# LCmeter0-LCD-6pin.net
KiCad netlist of a schematic drawn in EAGLE
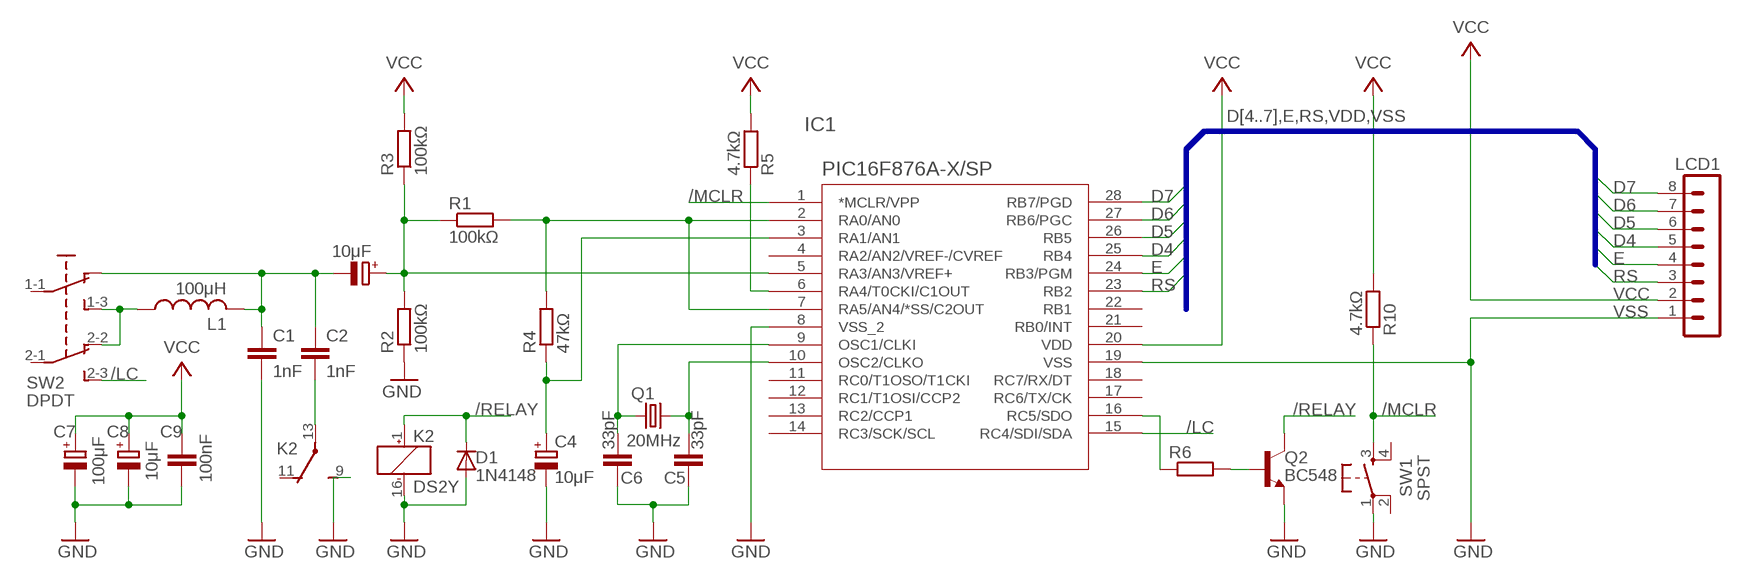
[diagram p0: schematic, sheet 1]

(export (version "E")
  (design (tool "Eeschema 10.0.6"))
  (components
    (comp (ref "C1")
      (value "1nF")
      (footprint "eagle-import:C050-025X075")
      (libsource (lib "eagle-import") (part "C-EU050-025X075"))
    )
    (comp (ref "C2")
      (value "1nF")
      (footprint "eagle-import:C050-025X075")
      (libsource (lib "eagle-import") (part "C-EU050-025X075"))
    )
    (comp (ref "C3")
      (value "10μF")
      (footprint "eagle-import:E2,5-6")
      (libsource (lib "eagle-import") (part "CPOL-EUE2.5-6"))
    )
    (comp (ref "C4")
      (value "10μF")
      (footprint "eagle-import:E5-6")
      (libsource (lib "eagle-import") (part "CPOL-EUE5-6"))
    )
    (comp (ref "C5")
      (value "33pF")
      (footprint "eagle-import:C050-025X075")
      (libsource (lib "eagle-import") (part "C-EU050-025X075"))
    )
    (comp (ref "C6")
      (value "33pF")
      (footprint "eagle-import:C050-025X075")
      (libsource (lib "eagle-import") (part "C-EU050-025X075"))
    )
    (comp (ref "C7")
      (value "100μF")
      (footprint "eagle-import:E2,5-6")
      (libsource (lib "eagle-import") (part "CPOL-EUE2.5-6"))
    )
    (comp (ref "C8")
      (value "10μF")
      (footprint "eagle-import:E2,5-5")
      (libsource (lib "eagle-import") (part "CPOL-EUE2.5-5"))
    )
    (comp (ref "C9")
      (value "100nF")
      (footprint "eagle-import:C025-024X044")
      (libsource (lib "eagle-import") (part "C-EU025-024X044"))
    )
    (comp (ref "D1")
      (value "1N4148")
      (footprint "eagle-import:DO35-7")
      (libsource (lib "eagle-import") (part "1N4148DO35-7"))
    )
    (comp (ref "IC1")
      (value "PIC16F876A-X/SP")
      (footprint "eagle-import:DIL28-3")
      (libsource (lib "eagle-import") (part "PIC16F876A-X/SP"))
    )
    (comp (ref "K2")
      (value "DS2Y")
      (footprint "eagle-import:DS2Y")
      (fields (field (name "MPN") "DS2Y-S-DC5V"))
      (libsource (lib "eagle-import") (part "DS2Y-S-DC5V"))
    )
    (comp (ref "L1")
      (value "100μH")
      (footprint "eagle-import:0207_10")
      (libsource (lib "eagle-import") (part "L-US0207/10"))
    )
    (comp (ref "LCD1")
      (value "MA08-1")
      (footprint "eagle-import:MA08-1")
      (libsource (lib "eagle-import") (part "MA08-1"))
    )
    (comp (ref "Q1")
      (value "20MHz")
      (footprint "eagle-import:HC49U70")
      (libsource (lib "eagle-import") (part "CRYSTALHC49U70"))
    )
    (comp (ref "Q2")
      (value "BC548")
      (footprint "eagle-import:TO92-EBC")
      (libsource (lib "eagle-import") (part "BC548"))
    )
    (comp (ref "R1")
      (value "100kΩ")
      (footprint "eagle-import:0207_10")
      (libsource (lib "eagle-import") (part "resistor_R-EU_0207/10"))
    )
    (comp (ref "R2")
      (value "100kΩ")
      (footprint "eagle-import:0207_10")
      (libsource (lib "eagle-import") (part "resistor_R-EU_0207/10"))
    )
    (comp (ref "R3")
      (value "100kΩ")
      (footprint "eagle-import:0204V")
      (libsource (lib "eagle-import") (part "resistor_R-EU_0204/2V"))
    )
    (comp (ref "R4")
      (value "47kΩ")
      (footprint "eagle-import:0207_10")
      (libsource (lib "eagle-import") (part "resistor_R-EU_0207/10"))
    )
    (comp (ref "R5")
      (value "4.7kΩ")
      (footprint "eagle-import:0204V")
      (libsource (lib "eagle-import") (part "resistor_R-EU_0204/2V"))
    )
    (comp (ref "R6")
      (value "R-EU_0207/10")
      (footprint "eagle-import:0207_10")
      (libsource (lib "eagle-import") (part "R-EU_0207/10"))
    )
    (comp (ref "R10")
      (value "4.7kΩ")
      (footprint "eagle-import:0204V")
      (libsource (lib "eagle-import") (part "resistor_R-EU_0204/2V"))
    )
    (comp (ref "SW1")
      (value "SPST")
      (footprint "eagle-import:PB-5")
      (libsource (lib "eagle-import") (part "PB-SPST"))
    )
    (comp (ref "SW2")
      (value "DPDT")
      (footprint "eagle-import:DPDT")
      (libsource (lib "eagle-import") (part "S-DPDT"))
    )
  )
  (nets
    (net (code "2") (name "/D4") (class "Default")
      (node (ref "IC1") (pin "25") (pinfunction "RB4_25") (pintype "passive"))
      (node (ref "LCD1") (pin "5") (pinfunction "5_5") (pintype "passive"))
    )
    (net (code "3") (name "/D5") (class "Default")
      (node (ref "IC1") (pin "26") (pinfunction "RB5_26") (pintype "passive"))
      (node (ref "LCD1") (pin "6") (pinfunction "6_6") (pintype "passive"))
    )
    (net (code "4") (name "/D6") (class "Default")
      (node (ref "IC1") (pin "27") (pinfunction "RB6/PGC_27") (pintype "passive"))
      (node (ref "LCD1") (pin "7") (pinfunction "7_7") (pintype "passive"))
    )
    (net (code "5") (name "/D7") (class "Default")
      (node (ref "IC1") (pin "28") (pinfunction "RB7/PGD_28") (pintype "passive"))
      (node (ref "LCD1") (pin "8") (pinfunction "8_8") (pintype "passive"))
    )
    (net (code "6") (name "/E") (class "Default")
      (node (ref "IC1") (pin "24") (pinfunction "RB3/PGM_24") (pintype "passive"))
      (node (ref "LCD1") (pin "4") (pinfunction "4_4") (pintype "passive"))
    )
    (net (code "7") (name "/RS") (class "Default")
      (node (ref "IC1") (pin "23") (pinfunction "RB2_23") (pintype "passive"))
      (node (ref "LCD1") (pin "3") (pinfunction "3_3") (pintype "passive"))
    )
    (net (code "9") (name "/{slash}LC") (class "Default")
      (node (ref "IC1") (pin "15") (pinfunction "RC4/SDI/SDA_15") (pintype "passive"))
      (node (ref "SW2") (pin "2-3") (pinfunction "2-3_2-3") (pintype "passive"))
    )
    (net (code "10") (name "/{slash}MCLR") (class "Default")
      (node (ref "IC1") (pin "1") (pinfunction "*MCLR/VPP_1") (pintype "passive"))
      (node (ref "R10") (pin "1") (pinfunction "1_1") (pintype "passive"))
      (node (ref "SW1") (pin "3") (pinfunction "S_3") (pintype "passive"))
    )
    (net (code "11") (name "/{slash}RELAY") (class "Default")
      (node (ref "D1") (pin "C") (pinfunction "C_C") (pintype "passive"))
      (node (ref "K2") (pin "1") (pinfunction "+_1") (pintype "passive"))
      (node (ref "Q2") (pin "C") (pinfunction "C_C") (pintype "passive"))
    )
    (net (code "12") (name "GND") (class "Default")
      (node (ref "C1") (pin "2") (pinfunction "2_2") (pintype "passive"))
      (node (ref "C4") (pin "-") (pinfunction "-_-") (pintype "passive"))
      (node (ref "C5") (pin "1") (pinfunction "1_1") (pintype "passive"))
      (node (ref "C6") (pin "1") (pinfunction "1_1") (pintype "passive"))
      (node (ref "C7") (pin "-") (pinfunction "-_-") (pintype "passive"))
      (node (ref "C8") (pin "-") (pinfunction "-_-") (pintype "passive"))
      (node (ref "C9") (pin "2") (pinfunction "2_2") (pintype "passive"))
      (node (ref "D1") (pin "A") (pinfunction "A_A") (pintype "passive"))
      (node (ref "IC1") (pin "19") (pinfunction "VSS_19") (pintype "passive"))
      (node (ref "IC1") (pin "8") (pinfunction "VSS_2_8") (pintype "passive"))
      (node (ref "K2") (pin "16") (pinfunction "-_16") (pintype "passive"))
      (node (ref "K2") (pin "9") (pinfunction "S_9") (pintype "passive"))
      (node (ref "LCD1") (pin "1") (pinfunction "1_1") (pintype "passive"))
      (node (ref "Q2") (pin "E") (pinfunction "E_E") (pintype "passive"))
      (node (ref "R2") (pin "1") (pinfunction "1_1") (pintype "passive"))
      (node (ref "SW1") (pin "1") (pinfunction "P_1") (pintype "passive"))
    )
    (net (code "13") (name "Net-(C1-Pad1)") (class "Default")
      (node (ref "C1") (pin "1") (pinfunction "1_1") (pintype "passive"))
      (node (ref "C2") (pin "1") (pinfunction "1_1") (pintype "passive"))
      (node (ref "C3") (pin "-") (pinfunction "-_-") (pintype "passive"))
      (node (ref "L1") (pin "2") (pinfunction "2_2") (pintype "passive"))
      (node (ref "SW2") (pin "1-2") (pinfunction "1-2_1-2") (pintype "passive"))
    )
    (net (code "14") (name "Net-(IC1-OSC1{slash}CLKI)") (class "Default")
      (node (ref "C6") (pin "2") (pinfunction "2_2") (pintype "passive"))
      (node (ref "IC1") (pin "9") (pinfunction "OSC1/CLKI_9") (pintype "passive"))
      (node (ref "Q1") (pin "1") (pinfunction "1_1") (pintype "passive"))
    )
    (net (code "15") (name "Net-(IC1-OSC2{slash}CLKO)") (class "Default")
      (node (ref "C5") (pin "2") (pinfunction "2_2") (pintype "passive"))
      (node (ref "IC1") (pin "10") (pinfunction "OSC2/CLKO_10") (pintype "passive"))
      (node (ref "Q1") (pin "2") (pinfunction "2_2") (pintype "passive"))
    )
    (net (code "16") (name "Net-(IC1-RA0{slash}AN0)") (class "Default")
      (node (ref "IC1") (pin "2") (pinfunction "RA0/AN0_2") (pintype "passive"))
      (node (ref "IC1") (pin "7") (pinfunction "RA5/AN4/*SS/C2OUT_7") (pintype "passive"))
      (node (ref "R1") (pin "2") (pinfunction "2_2") (pintype "passive"))
      (node (ref "R4") (pin "2") (pinfunction "2_2") (pintype "passive"))
    )
    (net (code "17") (name "Net-(IC1-RA1{slash}AN1)") (class "Default")
      (node (ref "C4") (pin "+") (pinfunction "+_+") (pintype "passive"))
      (node (ref "IC1") (pin "3") (pinfunction "RA1/AN1_3") (pintype "passive"))
      (node (ref "R4") (pin "1") (pinfunction "1_1") (pintype "passive"))
    )
    (net (code "18") (name "Net-(IC1-RA3{slash}AN3{slash}VREF+)") (class "Default")
      (node (ref "C3") (pin "+") (pinfunction "+_+") (pintype "passive"))
      (node (ref "IC1") (pin "5") (pinfunction "RA3/AN3/VREF+_5") (pintype "passive"))
      (node (ref "R1") (pin "1") (pinfunction "1_1") (pintype "passive"))
      (node (ref "R2") (pin "2") (pinfunction "2_2") (pintype "passive"))
      (node (ref "R3") (pin "1") (pinfunction "1_1") (pintype "passive"))
    )
    (net (code "19") (name "Net-(IC1-RA4{slash}T0CKI{slash}C1OUT)") (class "Default")
      (node (ref "IC1") (pin "6") (pinfunction "RA4/T0CKI/C1OUT_6") (pintype "passive"))
      (node (ref "R5") (pin "1") (pinfunction "1_1") (pintype "passive"))
    )
    (net (code "20") (name "Net-(IC1-RC5{slash}SDO)") (class "Default")
      (node (ref "IC1") (pin "16") (pinfunction "RC5/SDO_16") (pintype "passive"))
      (node (ref "R6") (pin "1") (pinfunction "1_1") (pintype "passive"))
    )
    (net (code "21") (name "Net-(K2C-P)") (class "Default")
      (node (ref "C2") (pin "2") (pinfunction "2_2") (pintype "passive"))
      (node (ref "K2") (pin "13") (pinfunction "P_13") (pintype "passive"))
    )
    (net (code "22") (name "Net-(L1-Pad1)") (class "Default")
      (node (ref "L1") (pin "1") (pinfunction "1_1") (pintype "passive"))
      (node (ref "SW2") (pin "1-3") (pinfunction "1-3_1-3") (pintype "passive"))
      (node (ref "SW2") (pin "2-2") (pinfunction "2-2_2-2") (pintype "passive"))
    )
    (net (code "23") (name "Net-(Q2-PadB)") (class "Default")
      (node (ref "Q2") (pin "B") (pinfunction "B_B") (pintype "passive"))
      (node (ref "R6") (pin "2") (pinfunction "2_2") (pintype "passive"))
    )
    (net (code "24") (name "VCC") (class "Default")
      (node (ref "C7") (pin "+") (pinfunction "+_+") (pintype "passive"))
      (node (ref "C8") (pin "+") (pinfunction "+_+") (pintype "passive"))
      (node (ref "C9") (pin "1") (pinfunction "1_1") (pintype "passive"))
      (node (ref "IC1") (pin "20") (pinfunction "VDD_20") (pintype "passive"))
      (node (ref "LCD1") (pin "2") (pinfunction "2_2") (pintype "passive"))
      (node (ref "R10") (pin "2") (pinfunction "2_2") (pintype "passive"))
      (node (ref "R3") (pin "2") (pinfunction "2_2") (pintype "passive"))
      (node (ref "R5") (pin "2") (pinfunction "2_2") (pintype "passive"))
    )
    (net (code "25") (name "unconnected-(IC1-RA2{slash}AN2{slash}VREF-{slash}CVREF-Pad4)") (class "Default")
      (node (ref "IC1") (pin "4") (pinfunction "RA2/AN2/VREF-/CVREF_4") (pintype "passive"))
    )
    (net (code "26") (name "unconnected-(IC1-RB0{slash}INT-Pad21)") (class "Default")
      (node (ref "IC1") (pin "21") (pinfunction "RB0/INT_21") (pintype "passive"))
    )
    (net (code "27") (name "unconnected-(IC1-RB1-Pad22)") (class "Default")
      (node (ref "IC1") (pin "22") (pinfunction "RB1_22") (pintype "passive"))
    )
    (net (code "28") (name "unconnected-(IC1-RC0{slash}T1OSO{slash}T1CKI-Pad11)") (class "Default")
      (node (ref "IC1") (pin "11") (pinfunction "RC0/T1OSO/T1CKI_11") (pintype "passive"))
    )
    (net (code "29") (name "unconnected-(IC1-RC1{slash}T1OSI{slash}CCP2-Pad12)") (class "Default")
      (node (ref "IC1") (pin "12") (pinfunction "RC1/T1OSI/CCP2_12") (pintype "passive"))
    )
    (net (code "30") (name "unconnected-(IC1-RC2{slash}CCP1-Pad13)") (class "Default")
      (node (ref "IC1") (pin "13") (pinfunction "RC2/CCP1_13") (pintype "passive"))
    )
    (net (code "31") (name "unconnected-(IC1-RC3{slash}SCK{slash}SCL-Pad14)") (class "Default")
      (node (ref "IC1") (pin "14") (pinfunction "RC3/SCK/SCL_14") (pintype "passive"))
    )
    (net (code "32") (name "unconnected-(IC1-RC6{slash}TX{slash}CK-Pad17)") (class "Default")
      (node (ref "IC1") (pin "17") (pinfunction "RC6/TX/CK_17") (pintype "passive"))
    )
    (net (code "33") (name "unconnected-(IC1-RC7{slash}RX{slash}DT-Pad18)") (class "Default")
      (node (ref "IC1") (pin "18") (pinfunction "RC7/RX/DT_18") (pintype "passive"))
    )
    (net (code "34") (name "unconnected-(K2C-O-Pad11)") (class "Default")
      (node (ref "K2") (pin "11") (pinfunction "O_11") (pintype "passive"))
    )
    (net (code "35") (name "unconnected-(SW1-P1-Pad2)") (class "Default")
      (node (ref "SW1") (pin "2") (pinfunction "P1_2") (pintype "passive"))
    )
    (net (code "36") (name "unconnected-(SW1-S1-Pad4)") (class "Default")
      (node (ref "SW1") (pin "4") (pinfunction "S1_4") (pintype "passive"))
    )
    (net (code "37") (name "unconnected-(SW2-Pad1-1)") (class "Default")
      (node (ref "SW2") (pin "1-1") (pinfunction "1-1_1-1") (pintype "passive"))
    )
    (net (code "38") (name "unconnected-(SW2-Pad2-1)") (class "Default")
      (node (ref "SW2") (pin "2-1") (pinfunction "2-1_2-1") (pintype "passive"))
    )
  )
)
